# untitled.net
KiCad netlist of a schematic drawn in EAGLE
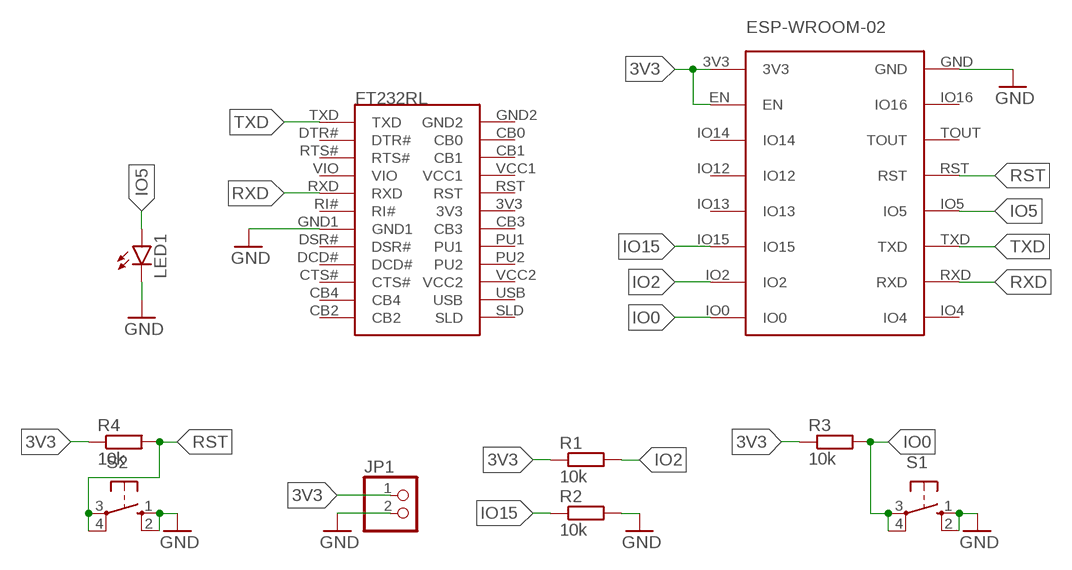
[diagram p0: schematic, sheet 1]

(export (version "E")
  (design (tool "Eeschema 10.0.6"))
  (components
    (comp (ref "ESP-WROOM-1")
      (value "ESP-WROOM-02")
      (footprint "eagle-import:ESP-WROOM-02")
      (libsource (lib "eagle-import") (part "ESP-WROOM-02"))
    )
    (comp (ref "FT232RL1")
      (value "FT232RL")
      (footprint "eagle-import:FT232RL")
      (libsource (lib "eagle-import") (part "FT232RL"))
    )
    (comp (ref "JP1")
      (value "PINHD-1X2")
      (footprint "eagle-import:1X02")
      (libsource (lib "eagle-import") (part "PINHD-1X2"))
    )
    (comp (ref "LED1")
      (value "LED5MM")
      (footprint "eagle-import:LED5MM")
      (libsource (lib "eagle-import") (part "LED5MM"))
    )
    (comp (ref "R1")
      (value "10k")
      (footprint "eagle-import:0204_7")
      (libsource (lib "eagle-import") (part "R-EU_0204/7"))
    )
    (comp (ref "R2")
      (value "10k")
      (footprint "eagle-import:0204_7")
      (libsource (lib "eagle-import") (part "R-EU_0204/7"))
    )
    (comp (ref "R3")
      (value "10k")
      (footprint "eagle-import:0204_7")
      (libsource (lib "eagle-import") (part "R-EU_0204/7"))
    )
    (comp (ref "R4")
      (value "10k")
      (footprint "eagle-import:0204_7")
      (libsource (lib "eagle-import") (part "R-EU_0204/7"))
    )
    (comp (ref "S1")
      (value "10-XX")
      (footprint "eagle-import:B3F-10XX")
      (fields (field (name "MPN") "B3F-1000"))
      (libsource (lib "eagle-import") (part "10-XX"))
    )
    (comp (ref "S2")
      (value "10-XX")
      (footprint "eagle-import:B3F-10XX")
      (fields (field (name "MPN") "B3F-1000"))
      (libsource (lib "eagle-import") (part "10-XX"))
    )
  )
  (nets
    (net (code "1") (name "3V3") (class "Default")
      (node (ref "ESP-WROOM-1") (pin "3V3") (pinfunction "3V3_3V3") (pintype "bidirectional"))
      (node (ref "ESP-WROOM-1") (pin "EN") (pinfunction "EN_EN") (pintype "bidirectional"))
      (node (ref "JP1") (pin "1") (pinfunction "1_1") (pintype "passive"))
      (node (ref "R1") (pin "1") (pinfunction "1_1") (pintype "passive"))
      (node (ref "R3") (pin "1") (pinfunction "1_1") (pintype "passive"))
      (node (ref "R4") (pin "1") (pinfunction "1_1") (pintype "passive"))
    )
    (net (code "2") (name "GND") (class "Default")
      (node (ref "ESP-WROOM-1") (pin "GND") (pinfunction "GND_GND") (pintype "bidirectional"))
      (node (ref "FT232RL1") (pin "GND1") (pinfunction "GND1_GND1") (pintype "bidirectional"))
      (node (ref "JP1") (pin "2") (pinfunction "2_2") (pintype "passive"))
      (node (ref "LED1") (pin "K") (pinfunction "C_K") (pintype "passive"))
      (node (ref "R2") (pin "2") (pinfunction "2_2") (pintype "passive"))
      (node (ref "S1") (pin "1") (pinfunction "S_1") (pintype "passive"))
      (node (ref "S1") (pin "2") (pinfunction "S1_2") (pintype "passive"))
      (node (ref "S2") (pin "1") (pinfunction "S_1") (pintype "passive"))
      (node (ref "S2") (pin "2") (pinfunction "S1_2") (pintype "passive"))
    )
    (net (code "3") (name "IO0") (class "Default")
      (node (ref "ESP-WROOM-1") (pin "IO0") (pinfunction "IO0_IO0") (pintype "bidirectional"))
      (node (ref "R3") (pin "2") (pinfunction "2_2") (pintype "passive"))
      (node (ref "S1") (pin "3") (pinfunction "P_3") (pintype "passive"))
      (node (ref "S1") (pin "4") (pinfunction "P1_4") (pintype "passive"))
    )
    (net (code "4") (name "IO2") (class "Default")
      (node (ref "ESP-WROOM-1") (pin "IO2") (pinfunction "IO2_IO2") (pintype "bidirectional"))
      (node (ref "R1") (pin "2") (pinfunction "2_2") (pintype "passive"))
    )
    (net (code "5") (name "IO5") (class "Default")
      (node (ref "ESP-WROOM-1") (pin "IO5") (pinfunction "IO5_IO5") (pintype "bidirectional"))
      (node (ref "LED1") (pin "A") (pinfunction "A_A") (pintype "passive"))
    )
    (net (code "6") (name "IO15") (class "Default")
      (node (ref "ESP-WROOM-1") (pin "IO15") (pinfunction "IO15_IO15") (pintype "bidirectional"))
      (node (ref "R2") (pin "1") (pinfunction "1_1") (pintype "passive"))
    )
    (net (code "7") (name "RST") (class "Default")
      (node (ref "ESP-WROOM-1") (pin "RST") (pinfunction "RST_RST") (pintype "bidirectional"))
      (node (ref "R4") (pin "2") (pinfunction "2_2") (pintype "passive"))
      (node (ref "S2") (pin "3") (pinfunction "P_3") (pintype "passive"))
      (node (ref "S2") (pin "4") (pinfunction "P1_4") (pintype "passive"))
    )
    (net (code "8") (name "RXD") (class "Default")
      (node (ref "ESP-WROOM-1") (pin "RXD") (pinfunction "RXD_RXD") (pintype "bidirectional"))
      (node (ref "FT232RL1") (pin "RXD") (pinfunction "RXD_RXD") (pintype "bidirectional"))
    )
    (net (code "9") (name "TXD") (class "Default")
      (node (ref "ESP-WROOM-1") (pin "TXD") (pinfunction "TXD_TXD") (pintype "bidirectional"))
      (node (ref "FT232RL1") (pin "TXD") (pinfunction "TXD_TXD") (pintype "bidirectional"))
    )
    (net (code "10") (name "unconnected-(ESP-WROOM-1-PadIO4)") (class "Default")
      (node (ref "ESP-WROOM-1") (pin "IO4") (pinfunction "IO4_IO4") (pintype "bidirectional"))
    )
    (net (code "11") (name "unconnected-(ESP-WROOM-1-PadIO12)") (class "Default")
      (node (ref "ESP-WROOM-1") (pin "IO12") (pinfunction "IO12_IO12") (pintype "bidirectional"))
    )
    (net (code "12") (name "unconnected-(ESP-WROOM-1-PadIO13)") (class "Default")
      (node (ref "ESP-WROOM-1") (pin "IO13") (pinfunction "IO13_IO13") (pintype "bidirectional"))
    )
    (net (code "13") (name "unconnected-(ESP-WROOM-1-PadIO14)") (class "Default")
      (node (ref "ESP-WROOM-1") (pin "IO14") (pinfunction "IO14_IO14") (pintype "bidirectional"))
    )
    (net (code "14") (name "unconnected-(ESP-WROOM-1-PadIO16)") (class "Default")
      (node (ref "ESP-WROOM-1") (pin "IO16") (pinfunction "IO16_IO16") (pintype "bidirectional"))
    )
    (net (code "15") (name "unconnected-(ESP-WROOM-1-PadTOUT)") (class "Default")
      (node (ref "ESP-WROOM-1") (pin "TOUT") (pinfunction "TOUT_TOUT") (pintype "bidirectional"))
    )
    (net (code "16") (name "unconnected-(FT232RL1-Pad3V3)") (class "Default")
      (node (ref "FT232RL1") (pin "3V3") (pinfunction "3V3_3V3") (pintype "bidirectional"))
    )
    (net (code "17") (name "unconnected-(FT232RL1-PadCB0)") (class "Default")
      (node (ref "FT232RL1") (pin "CB0") (pinfunction "CB0_CB0") (pintype "bidirectional"))
    )
    (net (code "18") (name "unconnected-(FT232RL1-PadCB1)") (class "Default")
      (node (ref "FT232RL1") (pin "CB1") (pinfunction "CB1_CB1") (pintype "bidirectional"))
    )
    (net (code "19") (name "unconnected-(FT232RL1-PadCB2)") (class "Default")
      (node (ref "FT232RL1") (pin "CB2") (pinfunction "CB2_CB2") (pintype "bidirectional"))
    )
    (net (code "20") (name "unconnected-(FT232RL1-PadCB3)") (class "Default")
      (node (ref "FT232RL1") (pin "CB3") (pinfunction "CB3_CB3") (pintype "bidirectional"))
    )
    (net (code "21") (name "unconnected-(FT232RL1-PadCB4)") (class "Default")
      (node (ref "FT232RL1") (pin "CB4") (pinfunction "CB4_CB4") (pintype "bidirectional"))
    )
    (net (code "22") (name "unconnected-(FT232RL1-PadCTS#)") (class "Default")
      (node (ref "FT232RL1") (pin "CTS#") (pinfunction "CTS#_CTS#") (pintype "bidirectional"))
    )
    (net (code "23") (name "unconnected-(FT232RL1-PadDCD#)") (class "Default")
      (node (ref "FT232RL1") (pin "DCD#") (pinfunction "DCD#_DCD#") (pintype "bidirectional"))
    )
    (net (code "24") (name "unconnected-(FT232RL1-PadDSR#)") (class "Default")
      (node (ref "FT232RL1") (pin "DSR#") (pinfunction "DSR#_DSR#") (pintype "bidirectional"))
    )
    (net (code "25") (name "unconnected-(FT232RL1-PadDTR#)") (class "Default")
      (node (ref "FT232RL1") (pin "DTR#") (pinfunction "DTR#_DTR#") (pintype "bidirectional"))
    )
    (net (code "26") (name "unconnected-(FT232RL1-PadGND2)") (class "Default")
      (node (ref "FT232RL1") (pin "GND2") (pinfunction "GND2_GND2") (pintype "bidirectional"))
    )
    (net (code "27") (name "unconnected-(FT232RL1-PadPU1)") (class "Default")
      (node (ref "FT232RL1") (pin "PU1") (pinfunction "PU1_PU1") (pintype "bidirectional"))
    )
    (net (code "28") (name "unconnected-(FT232RL1-PadPU2)") (class "Default")
      (node (ref "FT232RL1") (pin "PU2") (pinfunction "PU2_PU2") (pintype "bidirectional"))
    )
    (net (code "29") (name "unconnected-(FT232RL1-PadRI#)") (class "Default")
      (node (ref "FT232RL1") (pin "RI#") (pinfunction "RI#_RI#") (pintype "bidirectional"))
    )
    (net (code "30") (name "unconnected-(FT232RL1-PadRST)") (class "Default")
      (node (ref "FT232RL1") (pin "RST") (pinfunction "RST_RST") (pintype "bidirectional"))
    )
    (net (code "31") (name "unconnected-(FT232RL1-PadRTS#)") (class "Default")
      (node (ref "FT232RL1") (pin "RTS#") (pinfunction "RTS#_RTS#") (pintype "bidirectional"))
    )
    (net (code "32") (name "unconnected-(FT232RL1-PadSLD)") (class "Default")
      (node (ref "FT232RL1") (pin "SLD") (pinfunction "SLD_SLD") (pintype "bidirectional"))
    )
    (net (code "33") (name "unconnected-(FT232RL1-PadUSB)") (class "Default")
      (node (ref "FT232RL1") (pin "USB") (pinfunction "USB_USB") (pintype "bidirectional"))
    )
    (net (code "34") (name "unconnected-(FT232RL1-PadVCC1)") (class "Default")
      (node (ref "FT232RL1") (pin "VCC1") (pinfunction "VCC1_VCC1") (pintype "bidirectional"))
    )
    (net (code "35") (name "unconnected-(FT232RL1-PadVCC2)") (class "Default")
      (node (ref "FT232RL1") (pin "VCC2") (pinfunction "VCC2_VCC2") (pintype "bidirectional"))
    )
    (net (code "36") (name "unconnected-(FT232RL1-PadVIO)") (class "Default")
      (node (ref "FT232RL1") (pin "VIO") (pinfunction "VIO_VIO") (pintype "bidirectional"))
    )
  )
)
